# xns-ip67-ESP12-Temp.net
KiCad netlist of a schematic drawn in EAGLE
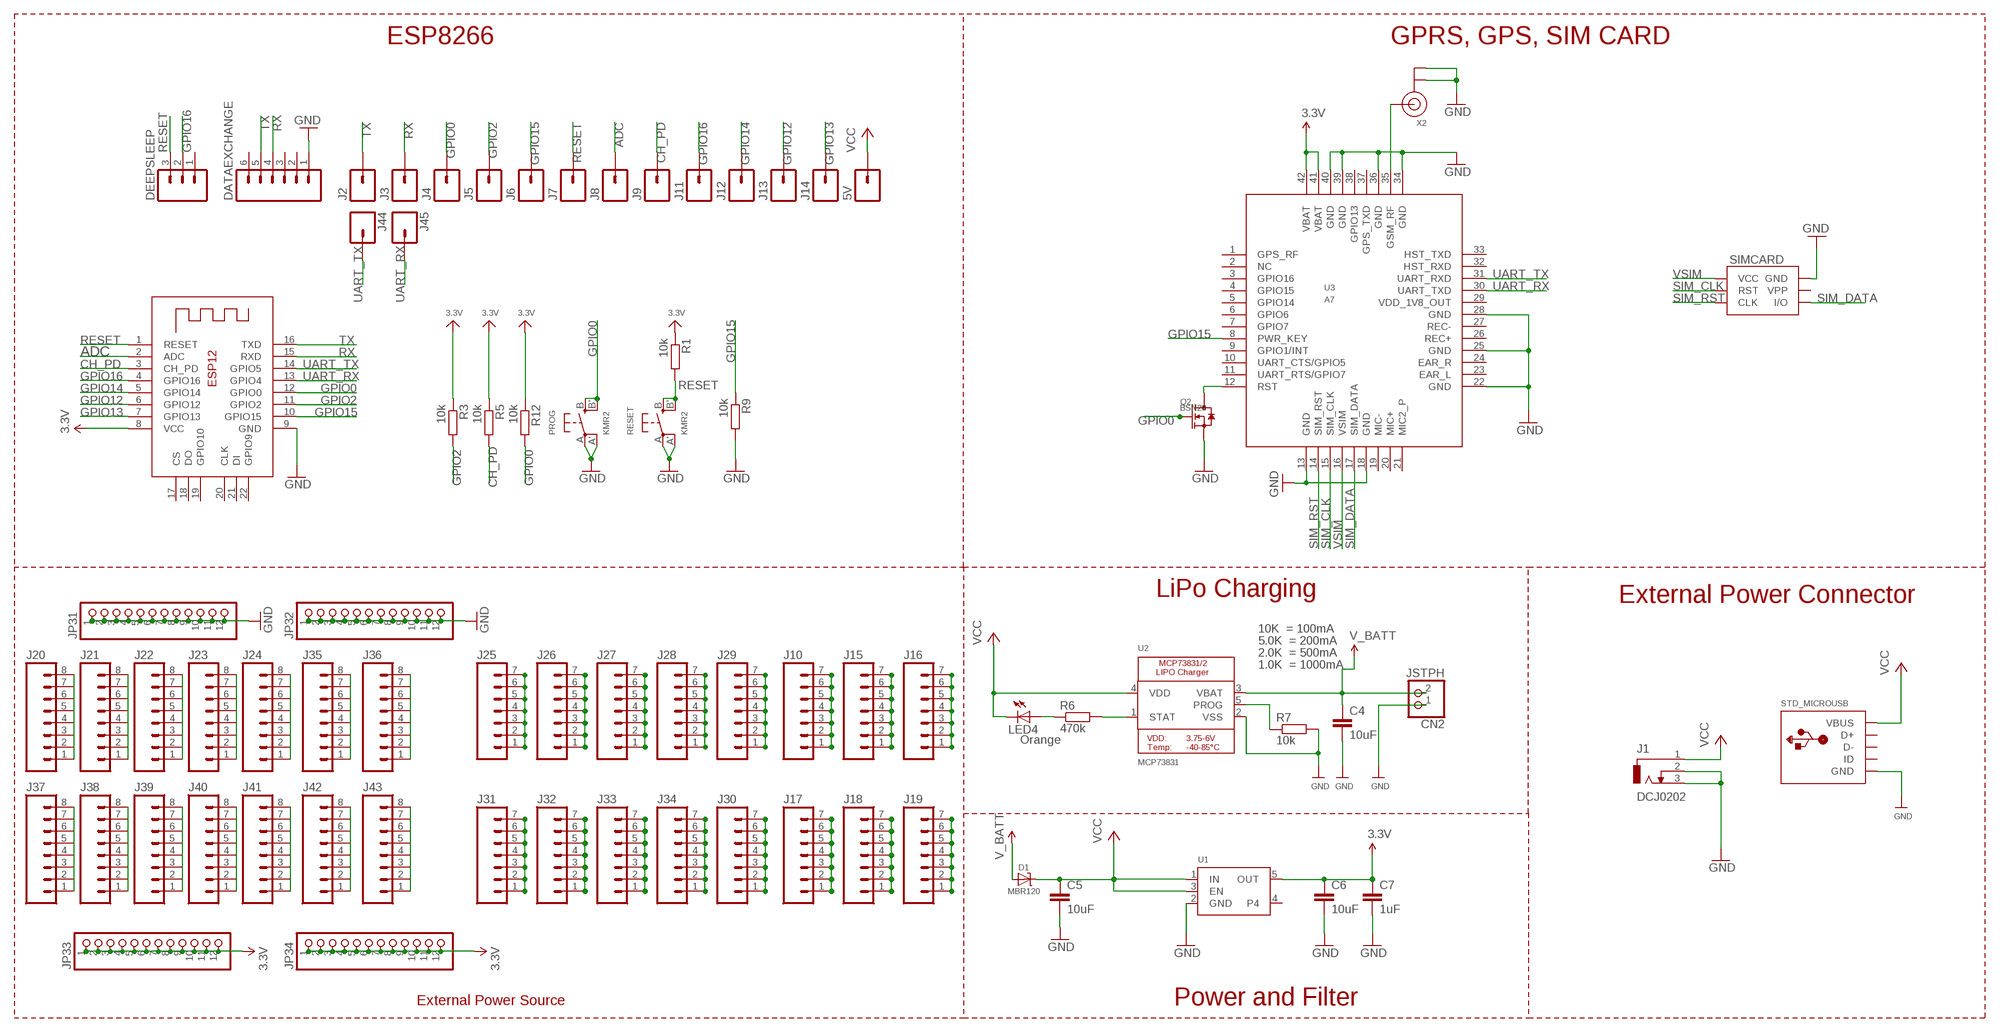
[diagram p0: schematic, sheet 1]

(export (version "E")
  (design (tool "Eeschema 10.0.6"))
  (components
    (comp (ref "5V")
      (value "M01NOSILK-KIT")
      (footprint "eagle-import:1X01NS-KIT")
      (libsource (lib "eagle-import") (part "M01NOSILK-KIT"))
    )
    (comp (ref "C4")
      (value "10uF")
      (footprint "eagle-import:C2.5-2")
      (libsource (lib "eagle-import") (part "C2.5/2"))
    )
    (comp (ref "C5")
      (value "10uF")
      (footprint "eagle-import:C2.5-2")
      (libsource (lib "eagle-import") (part "C2.5/2"))
    )
    (comp (ref "C6")
      (value "10uF")
      (footprint "eagle-import:C2.5-2")
      (libsource (lib "eagle-import") (part "C2.5/2"))
    )
    (comp (ref "C7")
      (value "1uF")
      (footprint "eagle-import:C2.5-2")
      (libsource (lib "eagle-import") (part "C2.5/2"))
    )
    (comp (ref "CN2")
      (value "JSTPH")
      (footprint "eagle-import:JSTPH2")
      (libsource (lib "eagle-import") (part "JST_2PIN"))
    )
    (comp (ref "D1")
      (value "MBR120")
      (footprint "eagle-import:SOD-123")
      (libsource (lib "eagle-import") (part "DIODE-SCHOTTKYSOD-123"))
    )
    (comp (ref "DATAEXCHANGE")
      (value "M06FEMALE_LOCK")
      (footprint "eagle-import:1X06_FEMALE_LOCK.010")
      (libsource (lib "eagle-import") (part "M06FEMALE_LOCK"))
    )
    (comp (ref "DEEPSLEEP")
      (value "M031X03_NO_SILK")
      (footprint "eagle-import:1X03_NO_SILK")
      (libsource (lib "eagle-import") (part "M031X03_NO_SILK"))
    )
    (comp (ref "J1")
      (value "DCJ0202")
      (footprint "eagle-import:DCJ0202")
      (libsource (lib "eagle-import") (part "DCJ0202"))
    )
    (comp (ref "J2")
      (value "M01NOSILK-KIT")
      (footprint "eagle-import:1X01NS-KIT")
      (libsource (lib "eagle-import") (part "M01NOSILK-KIT"))
    )
    (comp (ref "J3")
      (value "M01NOSILK-KIT")
      (footprint "eagle-import:1X01NS-KIT")
      (libsource (lib "eagle-import") (part "M01NOSILK-KIT"))
    )
    (comp (ref "J4")
      (value "M01NOSILK-KIT")
      (footprint "eagle-import:1X01NS-KIT")
      (libsource (lib "eagle-import") (part "M01NOSILK-KIT"))
    )
    (comp (ref "J5")
      (value "M01NOSILK-KIT")
      (footprint "eagle-import:1X01NS-KIT")
      (libsource (lib "eagle-import") (part "M01NOSILK-KIT"))
    )
    (comp (ref "J6")
      (value "M01NOSILK-KIT")
      (footprint "eagle-import:1X01NS-KIT")
      (libsource (lib "eagle-import") (part "M01NOSILK-KIT"))
    )
    (comp (ref "J7")
      (value "M01NOSILK-KIT")
      (footprint "eagle-import:1X01NS-KIT")
      (libsource (lib "eagle-import") (part "M01NOSILK-KIT"))
    )
    (comp (ref "J8")
      (value "M01NOSILK-KIT")
      (footprint "eagle-import:1X01NS-KIT")
      (libsource (lib "eagle-import") (part "M01NOSILK-KIT"))
    )
    (comp (ref "J9")
      (value "M01NOSILK-KIT")
      (footprint "eagle-import:1X01NS-KIT")
      (libsource (lib "eagle-import") (part "M01NOSILK-KIT"))
    )
    (comp (ref "J10")
      (value "M07NO_SILK")
      (footprint "eagle-import:1X07_NO_SILK")
      (libsource (lib "eagle-import") (part "M07NO_SILK"))
    )
    (comp (ref "J11")
      (value "M01NOSILK-KIT")
      (footprint "eagle-import:1X01NS-KIT")
      (libsource (lib "eagle-import") (part "M01NOSILK-KIT"))
    )
    (comp (ref "J12")
      (value "M01NOSILK-KIT")
      (footprint "eagle-import:1X01NS-KIT")
      (libsource (lib "eagle-import") (part "M01NOSILK-KIT"))
    )
    (comp (ref "J13")
      (value "M01NOSILK-KIT")
      (footprint "eagle-import:1X01NS-KIT")
      (libsource (lib "eagle-import") (part "M01NOSILK-KIT"))
    )
    (comp (ref "J14")
      (value "M01NOSILK-KIT")
      (footprint "eagle-import:1X01NS-KIT")
      (libsource (lib "eagle-import") (part "M01NOSILK-KIT"))
    )
    (comp (ref "J15")
      (value "M07NO_SILK")
      (footprint "eagle-import:1X07_NO_SILK")
      (libsource (lib "eagle-import") (part "M07NO_SILK"))
    )
    (comp (ref "J16")
      (value "M07NO_SILK")
      (footprint "eagle-import:1X07_NO_SILK")
      (libsource (lib "eagle-import") (part "M07NO_SILK"))
    )
    (comp (ref "J17")
      (value "M07NO_SILK")
      (footprint "eagle-import:1X07_NO_SILK")
      (libsource (lib "eagle-import") (part "M07NO_SILK"))
    )
    (comp (ref "J18")
      (value "M07NO_SILK")
      (footprint "eagle-import:1X07_NO_SILK")
      (libsource (lib "eagle-import") (part "M07NO_SILK"))
    )
    (comp (ref "J19")
      (value "M07NO_SILK")
      (footprint "eagle-import:1X07_NO_SILK")
      (libsource (lib "eagle-import") (part "M07NO_SILK"))
    )
    (comp (ref "J20")
      (value "M08NO_SILK_FEMALE_PTH")
      (footprint "eagle-import:1X08_NO_SILK")
      (libsource (lib "eagle-import") (part "M08NO_SILK_FEMALE_PTH"))
    )
    (comp (ref "J21")
      (value "M08NO_SILK_FEMALE_PTH")
      (footprint "eagle-import:1X08_NO_SILK")
      (libsource (lib "eagle-import") (part "M08NO_SILK_FEMALE_PTH"))
    )
    (comp (ref "J22")
      (value "M08NO_SILK_FEMALE_PTH")
      (footprint "eagle-import:1X08_NO_SILK")
      (libsource (lib "eagle-import") (part "M08NO_SILK_FEMALE_PTH"))
    )
    (comp (ref "J23")
      (value "M08NO_SILK_FEMALE_PTH")
      (footprint "eagle-import:1X08_NO_SILK")
      (libsource (lib "eagle-import") (part "M08NO_SILK_FEMALE_PTH"))
    )
    (comp (ref "J24")
      (value "M08NO_SILK_FEMALE_PTH")
      (footprint "eagle-import:1X08_NO_SILK")
      (libsource (lib "eagle-import") (part "M08NO_SILK_FEMALE_PTH"))
    )
    (comp (ref "J25")
      (value "M07NO_SILK")
      (footprint "eagle-import:1X07_NO_SILK")
      (libsource (lib "eagle-import") (part "M07NO_SILK"))
    )
    (comp (ref "J26")
      (value "M07NO_SILK")
      (footprint "eagle-import:1X07_NO_SILK")
      (libsource (lib "eagle-import") (part "M07NO_SILK"))
    )
    (comp (ref "J27")
      (value "M07NO_SILK")
      (footprint "eagle-import:1X07_NO_SILK")
      (libsource (lib "eagle-import") (part "M07NO_SILK"))
    )
    (comp (ref "J28")
      (value "M07NO_SILK")
      (footprint "eagle-import:1X07_NO_SILK")
      (libsource (lib "eagle-import") (part "M07NO_SILK"))
    )
    (comp (ref "J29")
      (value "M07NO_SILK")
      (footprint "eagle-import:1X07_NO_SILK")
      (libsource (lib "eagle-import") (part "M07NO_SILK"))
    )
    (comp (ref "J30")
      (value "M07NO_SILK")
      (footprint "eagle-import:1X07_NO_SILK")
      (libsource (lib "eagle-import") (part "M07NO_SILK"))
    )
    (comp (ref "J31")
      (value "M07NO_SILK")
      (footprint "eagle-import:1X07_NO_SILK")
      (libsource (lib "eagle-import") (part "M07NO_SILK"))
    )
    (comp (ref "J32")
      (value "M07NO_SILK")
      (footprint "eagle-import:1X07_NO_SILK")
      (libsource (lib "eagle-import") (part "M07NO_SILK"))
    )
    (comp (ref "J33")
      (value "M07NO_SILK")
      (footprint "eagle-import:1X07_NO_SILK")
      (libsource (lib "eagle-import") (part "M07NO_SILK"))
    )
    (comp (ref "J34")
      (value "M07NO_SILK")
      (footprint "eagle-import:1X07_NO_SILK")
      (libsource (lib "eagle-import") (part "M07NO_SILK"))
    )
    (comp (ref "J35")
      (value "M08NO_SILK_FEMALE_PTH")
      (footprint "eagle-import:1X08_NO_SILK")
      (libsource (lib "eagle-import") (part "M08NO_SILK_FEMALE_PTH"))
    )
    (comp (ref "J36")
      (value "M08NO_SILK_FEMALE_PTH")
      (footprint "eagle-import:1X08_NO_SILK")
      (libsource (lib "eagle-import") (part "M08NO_SILK_FEMALE_PTH"))
    )
    (comp (ref "J37")
      (value "M08NO_SILK_FEMALE_PTH")
      (footprint "eagle-import:1X08_NO_SILK")
      (libsource (lib "eagle-import") (part "M08NO_SILK_FEMALE_PTH"))
    )
    (comp (ref "J38")
      (value "M08NO_SILK_FEMALE_PTH")
      (footprint "eagle-import:1X08_NO_SILK")
      (libsource (lib "eagle-import") (part "M08NO_SILK_FEMALE_PTH"))
    )
    (comp (ref "J39")
      (value "M08NO_SILK_FEMALE_PTH")
      (footprint "eagle-import:1X08_NO_SILK")
      (libsource (lib "eagle-import") (part "M08NO_SILK_FEMALE_PTH"))
    )
    (comp (ref "J40")
      (value "M08NO_SILK_FEMALE_PTH")
      (footprint "eagle-import:1X08_NO_SILK")
      (libsource (lib "eagle-import") (part "M08NO_SILK_FEMALE_PTH"))
    )
    (comp (ref "J41")
      (value "M08NO_SILK_FEMALE_PTH")
      (footprint "eagle-import:1X08_NO_SILK")
      (libsource (lib "eagle-import") (part "M08NO_SILK_FEMALE_PTH"))
    )
    (comp (ref "J42")
      (value "M08NO_SILK_FEMALE_PTH")
      (footprint "eagle-import:1X08_NO_SILK")
      (libsource (lib "eagle-import") (part "M08NO_SILK_FEMALE_PTH"))
    )
    (comp (ref "J43")
      (value "M08NO_SILK_FEMALE_PTH")
      (footprint "eagle-import:1X08_NO_SILK")
      (libsource (lib "eagle-import") (part "M08NO_SILK_FEMALE_PTH"))
    )
    (comp (ref "J44")
      (value "M01NOSILK-KIT")
      (footprint "eagle-import:1X01NS-KIT")
      (libsource (lib "eagle-import") (part "M01NOSILK-KIT"))
    )
    (comp (ref "J45")
      (value "M01NOSILK-KIT")
      (footprint "eagle-import:1X01NS-KIT")
      (libsource (lib "eagle-import") (part "M01NOSILK-KIT"))
    )
    (comp (ref "JP31")
      (value "HEADER-1X12")
      (footprint "eagle-import:1X12_ROUND")
      (libsource (lib "eagle-import") (part "HEADER-1X12"))
    )
    (comp (ref "JP32")
      (value "HEADER-1X12")
      (footprint "eagle-import:1X12_ROUND")
      (libsource (lib "eagle-import") (part "HEADER-1X12"))
    )
    (comp (ref "JP33")
      (value "HEADER-1X12")
      (footprint "eagle-import:1X12_ROUND")
      (libsource (lib "eagle-import") (part "HEADER-1X12"))
    )
    (comp (ref "JP34")
      (value "HEADER-1X12")
      (footprint "eagle-import:1X12_ROUND")
      (libsource (lib "eagle-import") (part "HEADER-1X12"))
    )
    (comp (ref "LED4")
      (value "Orange")
      (footprint "eagle-import:LED5MM")
      (libsource (lib "eagle-import") (part "LED5MM"))
    )
    (comp (ref "PROG")
      (value "KMR2")
      (footprint "eagle-import:BTN_KMR2_4.6X2.8")
      (libsource (lib "eagle-import") (part "SWITCH_TACT_SMT4.6X2.8"))
    )
    (comp (ref "Q2")
      (value "BSN20")
      (footprint "eagle-import:SOT23@1")
      (libsource (lib "eagle-import") (part "MOSFET-N'SOT23'"))
    )
    (comp (ref "R1")
      (value "10k")
      (footprint "eagle-import:0204_7")
      (libsource (lib "eagle-import") (part "R0204/7"))
    )
    (comp (ref "R3")
      (value "10k")
      (footprint "eagle-import:0204_7")
      (libsource (lib "eagle-import") (part "R0204/7"))
    )
    (comp (ref "R5")
      (value "10k")
      (footprint "eagle-import:0204_7")
      (libsource (lib "eagle-import") (part "R0204/7"))
    )
    (comp (ref "R6")
      (value "470k")
      (footprint "eagle-import:0204_7")
      (libsource (lib "eagle-import") (part "R0204/7"))
    )
    (comp (ref "R7")
      (value "10k")
      (footprint "eagle-import:0204_7")
      (libsource (lib "eagle-import") (part "R0204/7"))
    )
    (comp (ref "R9")
      (value "10k")
      (footprint "eagle-import:0204_7")
      (libsource (lib "eagle-import") (part "R0204/7"))
    )
    (comp (ref "R12")
      (value "10k")
      (footprint "eagle-import:0204_7")
      (libsource (lib "eagle-import") (part "R0204/7"))
    )
    (comp (ref "RESET")
      (value "KMR2")
      (footprint "eagle-import:BTN_KMR2_4.6X2.8")
      (libsource (lib "eagle-import") (part "SWITCH_TACT_SMT4.6X2.8"))
    )
    (comp (ref "SIMCARD")
      (value "SIMHOLDERSIM")
      (footprint "eagle-import:SIMHOLDER")
      (libsource (lib "eagle-import") (part "SIMHOLDERSIM"))
    )
    (comp (ref "STD_MICROUSB")
      (value "USB_MICRO_20329_V2")
      (footprint "eagle-import:4UCONN_20329_V2")
      (libsource (lib "eagle-import") (part "USB_MICRO_20329_V2"))
    )
    (comp (ref "U1")
      (value "VREG_SOT23-5")
      (footprint "eagle-import:SOT23-5")
      (libsource (lib "eagle-import") (part "VREG_SOT23-5"))
    )
    (comp (ref "U2")
      (value "MCP73831")
      (footprint "eagle-import:SOT23-5@1")
      (libsource (lib "eagle-import") (part "MCP73831/2"))
    )
    (comp (ref "U3") (value "A7") (footprint "eagle-import:A7") (libsource (lib "eagle-import") (part "A7")))
    (comp (ref "X1")
      (value "ESP-12E")
      (footprint "eagle-import:ESP-12E")
      (libsource (lib "eagle-import") (part "ESP-12E"))
    )
    (comp (ref "X2")
      (value "ANTENNA_U.FL")
      (footprint "eagle-import:U.FL")
      (libsource (lib "eagle-import") (part "ANTENNA_U.FL"))
    )
  )
  (nets
    (net (code "1") (name "/ADC") (class "Default")
      (node (ref "J8") (pin "1") (pinfunction "1_1") (pintype "passive"))
      (node (ref "X1") (pin "2") (pinfunction "ADC_2") (pintype "passive"))
    )
    (net (code "2") (name "/CH_PD") (class "Default")
      (node (ref "J9") (pin "1") (pinfunction "1_1") (pintype "passive"))
      (node (ref "R5") (pin "2") (pinfunction "2_2") (pintype "passive"))
      (node (ref "X1") (pin "3") (pinfunction "CH_PD_3") (pintype "input"))
    )
    (net (code "3") (name "/GPIO0") (class "Default")
      (node (ref "J4") (pin "1") (pinfunction "1_1") (pintype "passive"))
      (node (ref "PROG") (pin "B") (pinfunction "S_B") (pintype "passive"))
      (node (ref "PROG") (pin "B'") (pinfunction "S1_B'") (pintype "passive"))
      (node (ref "Q2") (pin "1") (pinfunction "G_1") (pintype "passive"))
      (node (ref "R12") (pin "2") (pinfunction "2_2") (pintype "passive"))
      (node (ref "X1") (pin "12") (pinfunction "GPIO0_12") (pintype "bidirectional"))
    )
    (net (code "4") (name "/GPIO2") (class "Default")
      (node (ref "J5") (pin "1") (pinfunction "1_1") (pintype "passive"))
      (node (ref "R3") (pin "2") (pinfunction "2_2") (pintype "passive"))
      (node (ref "X1") (pin "11") (pinfunction "GPIO2_11") (pintype "bidirectional"))
    )
    (net (code "5") (name "/GPIO12") (class "Default")
      (node (ref "J13") (pin "1") (pinfunction "1_1") (pintype "passive"))
      (node (ref "X1") (pin "6") (pinfunction "GPIO12_6") (pintype "bidirectional"))
    )
    (net (code "6") (name "/GPIO13") (class "Default")
      (node (ref "J14") (pin "1") (pinfunction "1_1") (pintype "passive"))
      (node (ref "X1") (pin "7") (pinfunction "GPIO13_7") (pintype "bidirectional"))
    )
    (net (code "7") (name "/GPIO14") (class "Default")
      (node (ref "J12") (pin "1") (pinfunction "1_1") (pintype "passive"))
      (node (ref "X1") (pin "5") (pinfunction "GPIO14_5") (pintype "bidirectional"))
    )
    (net (code "8") (name "/GPIO15") (class "Default")
      (node (ref "J6") (pin "1") (pinfunction "1_1") (pintype "passive"))
      (node (ref "R9") (pin "1") (pinfunction "1_1") (pintype "passive"))
      (node (ref "U3") (pin "8") (pinfunction "PWR_KEY_8") (pintype "bidirectional"))
      (node (ref "X1") (pin "10") (pinfunction "GPIO15_10") (pintype "bidirectional"))
    )
    (net (code "9") (name "/GPIO16") (class "Default")
      (node (ref "DEEPSLEEP") (pin "2") (pinfunction "2_2") (pintype "passive"))
      (node (ref "J11") (pin "1") (pinfunction "1_1") (pintype "passive"))
      (node (ref "X1") (pin "4") (pinfunction "GPIO16_4") (pintype "bidirectional"))
    )
    (net (code "10") (name "/RESET") (class "Default")
      (node (ref "DEEPSLEEP") (pin "3") (pinfunction "3_3") (pintype "passive"))
      (node (ref "J7") (pin "1") (pinfunction "1_1") (pintype "passive"))
      (node (ref "R1") (pin "2") (pinfunction "2_2") (pintype "passive"))
      (node (ref "RESET") (pin "B") (pinfunction "S_B") (pintype "passive"))
      (node (ref "RESET") (pin "B'") (pinfunction "S1_B'") (pintype "passive"))
      (node (ref "X1") (pin "1") (pinfunction "RESET_1") (pintype "input"))
    )
    (net (code "11") (name "/RX") (class "Default")
      (node (ref "DATAEXCHANGE") (pin "4") (pinfunction "4_4") (pintype "passive"))
      (node (ref "J3") (pin "1") (pinfunction "1_1") (pintype "passive"))
      (node (ref "X1") (pin "15") (pinfunction "RXD_15") (pintype "input"))
    )
    (net (code "12") (name "/SIM_CLK") (class "Default")
      (node (ref "SIMCARD") (pin "C2") (pinfunction "RST_C2") (pintype "input"))
      (node (ref "U3") (pin "15") (pinfunction "SIM_CLK_15") (pintype "bidirectional"))
    )
    (net (code "13") (name "/SIM_DATA") (class "Default")
      (node (ref "SIMCARD") (pin "C7") (pinfunction "I/O_C7") (pintype "bidirectional"))
      (node (ref "U3") (pin "17") (pinfunction "SIM_DATA_17") (pintype "bidirectional"))
    )
    (net (code "14") (name "/SIM_RST") (class "Default")
      (node (ref "SIMCARD") (pin "C3") (pinfunction "CLK_C3") (pintype "input"))
      (node (ref "U3") (pin "14") (pinfunction "SIM_RST_14") (pintype "bidirectional"))
    )
    (net (code "15") (name "/TX") (class "Default")
      (node (ref "DATAEXCHANGE") (pin "5") (pinfunction "5_5") (pintype "passive"))
      (node (ref "J2") (pin "1") (pinfunction "1_1") (pintype "passive"))
      (node (ref "X1") (pin "16") (pinfunction "TXD_16") (pintype "output"))
    )
    (net (code "16") (name "/UART_RX") (class "Default")
      (node (ref "J45") (pin "1") (pinfunction "1_1") (pintype "passive"))
      (node (ref "U3") (pin "30") (pinfunction "UART_TXD_30") (pintype "bidirectional"))
      (node (ref "X1") (pin "13") (pinfunction "GPIO4_13") (pintype "bidirectional"))
    )
    (net (code "17") (name "/UART_TX") (class "Default")
      (node (ref "J44") (pin "1") (pinfunction "1_1") (pintype "passive"))
      (node (ref "U3") (pin "31") (pinfunction "UART_RXD_31") (pintype "bidirectional"))
      (node (ref "X1") (pin "14") (pinfunction "GPIO5_14") (pintype "bidirectional"))
    )
    (net (code "18") (name "/VSIM") (class "Default")
      (node (ref "SIMCARD") (pin "C1") (pinfunction "VCC_C1") (pintype "power_in"))
      (node (ref "U3") (pin "16") (pinfunction "VSIM_16") (pintype "bidirectional"))
    )
    (net (code "19") (name "3.3V") (class "Default")
      (node (ref "C6") (pin "1") (pinfunction "1_1") (pintype "passive"))
      (node (ref "C7") (pin "1") (pinfunction "1_1") (pintype "passive"))
      (node (ref "JP33") (pin "1") (pinfunction "1_1") (pintype "passive"))
      (node (ref "JP33") (pin "10") (pinfunction "10_10") (pintype "passive"))
      (node (ref "JP33") (pin "11") (pinfunction "11_11") (pintype "passive"))
      (node (ref "JP33") (pin "12") (pinfunction "12_12") (pintype "passive"))
      (node (ref "JP33") (pin "2") (pinfunction "2_2") (pintype "passive"))
      (node (ref "JP33") (pin "3") (pinfunction "3_3") (pintype "passive"))
      (node (ref "JP33") (pin "4") (pinfunction "4_4") (pintype "passive"))
      (node (ref "JP33") (pin "5") (pinfunction "5_5") (pintype "passive"))
      (node (ref "JP33") (pin "6") (pinfunction "6_6") (pintype "passive"))
      (node (ref "JP33") (pin "7") (pinfunction "7_7") (pintype "passive"))
      (node (ref "JP33") (pin "8") (pinfunction "8_8") (pintype "passive"))
      (node (ref "JP33") (pin "9") (pinfunction "9_9") (pintype "passive"))
      (node (ref "JP34") (pin "1") (pinfunction "1_1") (pintype "passive"))
      (node (ref "JP34") (pin "10") (pinfunction "10_10") (pintype "passive"))
      (node (ref "JP34") (pin "11") (pinfunction "11_11") (pintype "passive"))
      (node (ref "JP34") (pin "12") (pinfunction "12_12") (pintype "passive"))
      (node (ref "JP34") (pin "2") (pinfunction "2_2") (pintype "passive"))
      (node (ref "JP34") (pin "3") (pinfunction "3_3") (pintype "passive"))
      (node (ref "JP34") (pin "4") (pinfunction "4_4") (pintype "passive"))
      (node (ref "JP34") (pin "5") (pinfunction "5_5") (pintype "passive"))
      (node (ref "JP34") (pin "6") (pinfunction "6_6") (pintype "passive"))
      (node (ref "JP34") (pin "7") (pinfunction "7_7") (pintype "passive"))
      (node (ref "JP34") (pin "8") (pinfunction "8_8") (pintype "passive"))
      (node (ref "JP34") (pin "9") (pinfunction "9_9") (pintype "passive"))
      (node (ref "R1") (pin "1") (pinfunction "1_1") (pintype "passive"))
      (node (ref "R12") (pin "1") (pinfunction "1_1") (pintype "passive"))
      (node (ref "R3") (pin "1") (pinfunction "1_1") (pintype "passive"))
      (node (ref "R5") (pin "1") (pinfunction "1_1") (pintype "passive"))
      (node (ref "U1") (pin "5") (pinfunction "OUT_5") (pintype "power_in"))
      (node (ref "U3") (pin "41") (pinfunction "VBAT_41") (pintype "bidirectional"))
      (node (ref "U3") (pin "42") (pinfunction "VBAT_42") (pintype "bidirectional"))
      (node (ref "X1") (pin "8") (pinfunction "VCC_8") (pintype "power_in"))
    )
    (net (code "20") (name "GND") (class "Default")
      (node (ref "C4") (pin "2") (pinfunction "2_2") (pintype "passive"))
      (node (ref "C5") (pin "2") (pinfunction "2_2") (pintype "passive"))
      (node (ref "C6") (pin "2") (pinfunction "2_2") (pintype "passive"))
      (node (ref "C7") (pin "2") (pinfunction "2_2") (pintype "passive"))
      (node (ref "CN2") (pin "1") (pinfunction "1_1") (pintype "passive"))
      (node (ref "DATAEXCHANGE") (pin "1") (pinfunction "1_1") (pintype "passive"))
      (node (ref "J1") (pin "2") (pinfunction "2_2") (pintype "passive"))
      (node (ref "J1") (pin "3") (pinfunction "3_3") (pintype "passive"))
      (node (ref "JP31") (pin "1") (pinfunction "1_1") (pintype "passive"))
      (node (ref "JP31") (pin "10") (pinfunction "10_10") (pintype "passive"))
      (node (ref "JP31") (pin "11") (pinfunction "11_11") (pintype "passive"))
      (node (ref "JP31") (pin "12") (pinfunction "12_12") (pintype "passive"))
      (node (ref "JP31") (pin "2") (pinfunction "2_2") (pintype "passive"))
      (node (ref "JP31") (pin "3") (pinfunction "3_3") (pintype "passive"))
      (node (ref "JP31") (pin "4") (pinfunction "4_4") (pintype "passive"))
      (node (ref "JP31") (pin "5") (pinfunction "5_5") (pintype "passive"))
      (node (ref "JP31") (pin "6") (pinfunction "6_6") (pintype "passive"))
      (node (ref "JP31") (pin "7") (pinfunction "7_7") (pintype "passive"))
      (node (ref "JP31") (pin "8") (pinfunction "8_8") (pintype "passive"))
      (node (ref "JP31") (pin "9") (pinfunction "9_9") (pintype "passive"))
      (node (ref "JP32") (pin "1") (pinfunction "1_1") (pintype "passive"))
      (node (ref "JP32") (pin "10") (pinfunction "10_10") (pintype "passive"))
      (node (ref "JP32") (pin "11") (pinfunction "11_11") (pintype "passive"))
      (node (ref "JP32") (pin "12") (pinfunction "12_12") (pintype "passive"))
      (node (ref "JP32") (pin "2") (pinfunction "2_2") (pintype "passive"))
      (node (ref "JP32") (pin "3") (pinfunction "3_3") (pintype "passive"))
      (node (ref "JP32") (pin "4") (pinfunction "4_4") (pintype "passive"))
      (node (ref "JP32") (pin "5") (pinfunction "5_5") (pintype "passive"))
      (node (ref "JP32") (pin "6") (pinfunction "6_6") (pintype "passive"))
      (node (ref "JP32") (pin "7") (pinfunction "7_7") (pintype "passive"))
      (node (ref "JP32") (pin "8") (pinfunction "8_8") (pintype "passive"))
      (node (ref "JP32") (pin "9") (pinfunction "9_9") (pintype "passive"))
      (node (ref "PROG") (pin "A") (pinfunction "P_A") (pintype "passive"))
      (node (ref "PROG") (pin "A'") (pinfunction "P1_A'") (pintype "passive"))
      (node (ref "Q2") (pin "2") (pinfunction "S_2") (pintype "passive"))
      (node (ref "R7") (pin "2") (pinfunction "2_2") (pintype "passive"))
      (node (ref "R9") (pin "2") (pinfunction "2_2") (pintype "passive"))
      (node (ref "RESET") (pin "A") (pinfunction "P_A") (pintype "passive"))
      (node (ref "RESET") (pin "A'") (pinfunction "P1_A'") (pintype "passive"))
      (node (ref "SIMCARD") (pin "C5") (pinfunction "GND_C5") (pintype "power_in"))
      (node (ref "STD_MICROUSB") (pin "BASE@1") (pinfunction "GND_BASE@1") (pintype "power_in"))
      (node (ref "STD_MICROUSB") (pin "BASE@2") (pinfunction "GND_BASE@2") (pintype "power_in"))
      (node (ref "STD_MICROUSB") (pin "GND") (pinfunction "GND_GND") (pintype "power_in"))
      (node (ref "STD_MICROUSB") (pin "SPRT@1") (pinfunction "GND_SPRT@1") (pintype "power_in"))
      (node (ref "STD_MICROUSB") (pin "SPRT@2") (pinfunction "GND_SPRT@2") (pintype "power_in"))
      (node (ref "STD_MICROUSB") (pin "SPRT@3") (pinfunction "GND_SPRT@3") (pintype "power_in"))
      (node (ref "STD_MICROUSB") (pin "SPRT@4") (pinfunction "GND_SPRT@4") (pintype "power_in"))
      (node (ref "U1") (pin "2") (pinfunction "GND_2") (pintype "power_in"))
      (node (ref "U2") (pin "2") (pinfunction "VSS_2") (pintype "power_in"))
      (node (ref "U3") (pin "13") (pinfunction "GND_13") (pintype "bidirectional"))
      (node (ref "U3") (pin "18") (pinfunction "GND_18") (pintype "bidirectional"))
      (node (ref "U3") (pin "22") (pinfunction "GND_22") (pintype "bidirectional"))
      (node (ref "U3") (pin "25") (pinfunction "GND_25") (pintype "bidirectional"))
      (node (ref "U3") (pin "28") (pinfunction "GND_28") (pintype "bidirectional"))
      (node (ref "U3") (pin "34") (pinfunction "GND_34") (pintype "bidirectional"))
      (node (ref "U3") (pin "36") (pinfunction "GND_36") (pintype "bidirectional"))
      (node (ref "U3") (pin "39") (pinfunction "GND_39") (pintype "bidirectional"))
      (node (ref "U3") (pin "40") (pinfunction "GND_40") (pintype "bidirectional"))
      (node (ref "X1") (pin "9") (pinfunction "GND_9") (pintype "power_in"))
      (node (ref "X2") (pin "1") (pinfunction "GND_1") (pintype "passive"))
      (node (ref "X2") (pin "2") (pinfunction "GND_2") (pintype "passive"))
    )
    (net (code "21") (name "Net-(J10-Pad1)") (class "Default")
      (node (ref "J10") (pin "1") (pinfunction "1_1") (pintype "passive"))
      (node (ref "J10") (pin "2") (pinfunction "2_2") (pintype "passive"))
      (node (ref "J10") (pin "3") (pinfunction "3_3") (pintype "passive"))
      (node (ref "J10") (pin "4") (pinfunction "4_4") (pintype "passive"))
      (node (ref "J10") (pin "5") (pinfunction "5_5") (pintype "passive"))
      (node (ref "J10") (pin "6") (pinfunction "6_6") (pintype "passive"))
      (node (ref "J10") (pin "7") (pinfunction "7_7") (pintype "passive"))
    )
    (net (code "22") (name "Net-(J15-Pad1)") (class "Default")
      (node (ref "J15") (pin "1") (pinfunction "1_1") (pintype "passive"))
      (node (ref "J15") (pin "2") (pinfunction "2_2") (pintype "passive"))
      (node (ref "J15") (pin "3") (pinfunction "3_3") (pintype "passive"))
      (node (ref "J15") (pin "4") (pinfunction "4_4") (pintype "passive"))
      (node (ref "J15") (pin "5") (pinfunction "5_5") (pintype "passive"))
      (node (ref "J15") (pin "6") (pinfunction "6_6") (pintype "passive"))
      (node (ref "J15") (pin "7") (pinfunction "7_7") (pintype "passive"))
    )
    (net (code "23") (name "Net-(J16-Pad1)") (class "Default")
      (node (ref "J16") (pin "1") (pinfunction "1_1") (pintype "passive"))
      (node (ref "J16") (pin "2") (pinfunction "2_2") (pintype "passive"))
      (node (ref "J16") (pin "3") (pinfunction "3_3") (pintype "passive"))
      (node (ref "J16") (pin "4") (pinfunction "4_4") (pintype "passive"))
      (node (ref "J16") (pin "5") (pinfunction "5_5") (pintype "passive"))
      (node (ref "J16") (pin "6") (pinfunction "6_6") (pintype "passive"))
      (node (ref "J16") (pin "7") (pinfunction "7_7") (pintype "passive"))
    )
    (net (code "24") (name "Net-(J17-Pad1)") (class "Default")
      (node (ref "J17") (pin "1") (pinfunction "1_1") (pintype "passive"))
      (node (ref "J17") (pin "2") (pinfunction "2_2") (pintype "passive"))
      (node (ref "J17") (pin "3") (pinfunction "3_3") (pintype "passive"))
      (node (ref "J17") (pin "4") (pinfunction "4_4") (pintype "passive"))
      (node (ref "J17") (pin "5") (pinfunction "5_5") (pintype "passive"))
      (node (ref "J17") (pin "6") (pinfunction "6_6") (pintype "passive"))
      (node (ref "J17") (pin "7") (pinfunction "7_7") (pintype "passive"))
    )
    (net (code "25") (name "Net-(J18-Pad1)") (class "Default")
      (node (ref "J18") (pin "1") (pinfunction "1_1") (pintype "passive"))
      (node (ref "J18") (pin "2") (pinfunction "2_2") (pintype "passive"))
      (node (ref "J18") (pin "3") (pinfunction "3_3") (pintype "passive"))
      (node (ref "J18") (pin "4") (pinfunction "4_4") (pintype "passive"))
      (node (ref "J18") (pin "5") (pinfunction "5_5") (pintype "passive"))
      (node (ref "J18") (pin "6") (pinfunction "6_6") (pintype "passive"))
      (node (ref "J18") (pin "7") (pinfunction "7_7") (pintype "passive"))
    )
    (net (code "26") (name "Net-(J19-Pad1)") (class "Default")
      (node (ref "J19") (pin "1") (pinfunction "1_1") (pintype "passive"))
      (node (ref "J19") (pin "2") (pinfunction "2_2") (pintype "passive"))
      (node (ref "J19") (pin "3") (pinfunction "3_3") (pintype "passive"))
      (node (ref "J19") (pin "4") (pinfunction "4_4") (pintype "passive"))
      (node (ref "J19") (pin "5") (pinfunction "5_5") (pintype "passive"))
      (node (ref "J19") (pin "6") (pinfunction "6_6") (pintype "passive"))
      (node (ref "J19") (pin "7") (pinfunction "7_7") (pintype "passive"))
    )
    (net (code "27") (name "Net-(J20-Pad1)") (class "Default")
      (node (ref "J20") (pin "1") (pinfunction "1_1") (pintype "passive"))
      (node (ref "J20") (pin "2") (pinfunction "2_2") (pintype "passive"))
      (node (ref "J20") (pin "3") (pinfunction "3_3") (pintype "passive"))
      (node (ref "J20") (pin "4") (pinfunction "4_4") (pintype "passive"))
      (node (ref "J20") (pin "5") (pinfunction "5_5") (pintype "passive"))
      (node (ref "J20") (pin "6") (pinfunction "6_6") (pintype "passive"))
      (node (ref "J20") (pin "7") (pinfunction "7_7") (pintype "passive"))
      (node (ref "J20") (pin "8") (pinfunction "8_8") (pintype "passive"))
    )
    (net (code "28") (name "Net-(J21-Pad1)") (class "Default")
      (node (ref "J21") (pin "1") (pinfunction "1_1") (pintype "passive"))
      (node (ref "J21") (pin "2") (pinfunction "2_2") (pintype "passive"))
      (node (ref "J21") (pin "3") (pinfunction "3_3") (pintype "passive"))
      (node (ref "J21") (pin "4") (pinfunction "4_4") (pintype "passive"))
      (node (ref "J21") (pin "5") (pinfunction "5_5") (pintype "passive"))
      (node (ref "J21") (pin "6") (pinfunction "6_6") (pintype "passive"))
      (node (ref "J21") (pin "7") (pinfunction "7_7") (pintype "passive"))
      (node (ref "J21") (pin "8") (pinfunction "8_8") (pintype "passive"))
    )
    (net (code "29") (name "Net-(J22-Pad1)") (class "Default")
      (node (ref "J22") (pin "1") (pinfunction "1_1") (pintype "passive"))
      (node (ref "J22") (pin "2") (pinfunction "2_2") (pintype "passive"))
      (node (ref "J22") (pin "3") (pinfunction "3_3") (pintype "passive"))
      (node (ref "J22") (pin "4") (pinfunction "4_4") (pintype "passive"))
      (node (ref "J22") (pin "5") (pinfunction "5_5") (pintype "passive"))
      (node (ref "J22") (pin "6") (pinfunction "6_6") (pintype "passive"))
      (node (ref "J22") (pin "7") (pinfunction "7_7") (pintype "passive"))
      (node (ref "J22") (pin "8") (pinfunction "8_8") (pintype "passive"))
    )
    (net (code "30") (name "Net-(J23-Pad1)") (class "Default")
      (node (ref "J23") (pin "1") (pinfunction "1_1") (pintype "passive"))
      (node (ref "J23") (pin "2") (pinfunction "2_2") (pintype "passive"))
      (node (ref "J23") (pin "3") (pinfunction "3_3") (pintype "passive"))
      (node (ref "J23") (pin "4") (pinfunction "4_4") (pintype "passive"))
      (node (ref "J23") (pin "5") (pinfunction "5_5") (pintype "passive"))
      (node (ref "J23") (pin "6") (pinfunction "6_6") (pintype "passive"))
      (node (ref "J23") (pin "7") (pinfunction "7_7") (pintype "passive"))
      (node (ref "J23") (pin "8") (pinfunction "8_8") (pintype "passive"))
    )
    (net (code "31") (name "Net-(J24-Pad1)") (class "Default")
      (node (ref "J24") (pin "1") (pinfunction "1_1") (pintype "passive"))
      (node (ref "J24") (pin "2") (pinfunction "2_2") (pintype "passive"))
      (node (ref "J24") (pin "3") (pinfunction "3_3") (pintype "passive"))
      (node (ref "J24") (pin "4") (pinfunction "4_4") (pintype "passive"))
      (node (ref "J24") (pin "5") (pinfunction "5_5") (pintype "passive"))
      (node (ref "J24") (pin "6") (pinfunction "6_6") (pintype "passive"))
      (node (ref "J24") (pin "7") (pinfunction "7_7") (pintype "passive"))
      (node (ref "J24") (pin "8") (pinfunction "8_8") (pintype "passive"))
    )
    (net (code "32") (name "Net-(J25-Pad1)") (class "Default")
      (node (ref "J25") (pin "1") (pinfunction "1_1") (pintype "passive"))
      (node (ref "J25") (pin "2") (pinfunction "2_2") (pintype "passive"))
      (node (ref "J25") (pin "3") (pinfunction "3_3") (pintype "passive"))
      (node (ref "J25") (pin "4") (pinfunction "4_4") (pintype "passive"))
      (node (ref "J25") (pin "5") (pinfunction "5_5") (pintype "passive"))
      (node (ref "J25") (pin "6") (pinfunction "6_6") (pintype "passive"))
      (node (ref "J25") (pin "7") (pinfunction "7_7") (pintype "passive"))
    )
    (net (code "33") (name "Net-(J26-Pad1)") (class "Default")
      (node (ref "J26") (pin "1") (pinfunction "1_1") (pintype "passive"))
      (node (ref "J26") (pin "2") (pinfunction "2_2") (pintype "passive"))
      (node (ref "J26") (pin "3") (pinfunction "3_3") (pintype "passive"))
      (node (ref "J26") (pin "4") (pinfunction "4_4") (pintype "passive"))
      (node (ref "J26") (pin "5") (pinfunction "5_5") (pintype "passive"))
      (node (ref "J26") (pin "6") (pinfunction "6_6") (pintype "passive"))
      (node (ref "J26") (pin "7") (pinfunction "7_7") (pintype "passive"))
    )
    (net (code "34") (name "Net-(J27-Pad1)") (class "Default")
      (node (ref "J27") (pin "1") (pinfunction "1_1") (pintype "passive"))
      (node (ref "J27") (pin "2") (pinfunction "2_2") (pintype "passive"))
      (node (ref "J27") (pin "3") (pinfunction "3_3") (pintype "passive"))
      (node (ref "J27") (pin "4") (pinfunction "4_4") (pintype "passive"))
      (node (ref "J27") (pin "5") (pinfunction "5_5") (pintype "passive"))
      (node (ref "J27") (pin "6") (pinfunction "6_6") (pintype "passive"))
      (node (ref "J27") (pin "7") (pinfunction "7_7") (pintype "passive"))
    )
    (net (code "35") (name "Net-(J28-Pad1)") (class "Default")
      (node (ref "J28") (pin "1") (pinfunction "1_1") (pintype "passive"))
      (node (ref "J28") (pin "2") (pinfunction "2_2") (pintype "passive"))
      (node (ref "J28") (pin "3") (pinfunction "3_3") (pintype "passive"))
      (node (ref "J28") (pin "4") (pinfunction "4_4") (pintype "passive"))
      (node (ref "J28") (pin "5") (pinfunction "5_5") (pintype "passive"))
      (node (ref "J28") (pin "6") (pinfunction "6_6") (pintype "passive"))
      (node (ref "J28") (pin "7") (pinfunction "7_7") (pintype "passive"))
    )
    (net (code "36") (name "Net-(J29-Pad1)") (class "Default")
      (node (ref "J29") (pin "1") (pinfunction "1_1") (pintype "passive"))
      (node (ref "J29") (pin "2") (pinfunction "2_2") (pintype "passive"))
      (node (ref "J29") (pin "3") (pinfunction "3_3") (pintype "passive"))
      (node (ref "J29") (pin "4") (pinfunction "4_4") (pintype "passive"))
      (node (ref "J29") (pin "5") (pinfunction "5_5") (pintype "passive"))
      (node (ref "J29") (pin "6") (pinfunction "6_6") (pintype "passive"))
      (node (ref "J29") (pin "7") (pinfunction "7_7") (pintype "passive"))
    )
    (net (code "37") (name "Net-(J30-Pad1)") (class "Default")
      (node (ref "J30") (pin "1") (pinfunction "1_1") (pintype "passive"))
      (node (ref "J30") (pin "2") (pinfunction "2_2") (pintype "passive"))
      (node (ref "J30") (pin "3") (pinfunction "3_3") (pintype "passive"))
      (node (ref "J30") (pin "4") (pinfunction "4_4") (pintype "passive"))
      (node (ref "J30") (pin "5") (pinfunction "5_5") (pintype "passive"))
      (node (ref "J30") (pin "6") (pinfunction "6_6") (pintype "passive"))
      (node (ref "J30") (pin "7") (pinfunction "7_7") (pintype "passive"))
    )
    (net (code "38") (name "Net-(J31-Pad1)") (class "Default")
      (node (ref "J31") (pin "1") (pinfunction "1_1") (pintype "passive"))
      (node (ref "J31") (pin "2") (pinfunction "2_2") (pintype "passive"))
      (node (ref "J31") (pin "3") (pinfunction "3_3") (pintype "passive"))
      (node (ref "J31") (pin "4") (pinfunction "4_4") (pintype "passive"))
      (node (ref "J31") (pin "5") (pinfunction "5_5") (pintype "passive"))
      (node (ref "J31") (pin "6") (pinfunction "6_6") (pintype "passive"))
      (node (ref "J31") (pin "7") (pinfunction "7_7") (pintype "passive"))
    )
    (net (code "39") (name "Net-(J32-Pad1)") (class "Default")
      (node (ref "J32") (pin "1") (pinfunction "1_1") (pintype "passive"))
      (node (ref "J32") (pin "2") (pinfunction "2_2") (pintype "passive"))
      (node (ref "J32") (pin "3") (pinfunction "3_3") (pintype "passive"))
      (node (ref "J32") (pin "4") (pinfunction "4_4") (pintype "passive"))
      (node (ref "J32") (pin "5") (pinfunction "5_5") (pintype "passive"))
      (node (ref "J32") (pin "6") (pinfunction "6_6") (pintype "passive"))
      (node (ref "J32") (pin "7") (pinfunction "7_7") (pintype "passive"))
    )
    (net (code "40") (name "Net-(J33-Pad1)") (class "Default")
      (node (ref "J33") (pin "1") (pinfunction "1_1") (pintype "passive"))
      (node (ref "J33") (pin "2") (pinfunction "2_2") (pintype "passive"))
      (node (ref "J33") (pin "3") (pinfunction "3_3") (pintype "passive"))
      (node (ref "J33") (pin "4") (pinfunction "4_4") (pintype "passive"))
      (node (ref "J33") (pin "5") (pinfunction "5_5") (pintype "passive"))
      (node (ref "J33") (pin "6") (pinfunction "6_6") (pintype "passive"))
      (node (ref "J33") (pin "7") (pinfunction "7_7") (pintype "passive"))
    )
    (net (code "41") (name "Net-(J34-Pad1)") (class "Default")
      (node (ref "J34") (pin "1") (pinfunction "1_1") (pintype "passive"))
      (node (ref "J34") (pin "2") (pinfunction "2_2") (pintype "passive"))
      (node (ref "J34") (pin "3") (pinfunction "3_3") (pintype "passive"))
      (node (ref "J34") (pin "4") (pinfunction "4_4") (pintype "passive"))
      (node (ref "J34") (pin "5") (pinfunction "5_5") (pintype "passive"))
      (node (ref "J34") (pin "6") (pinfunction "6_6") (pintype "passive"))
      (node (ref "J34") (pin "7") (pinfunction "7_7") (pintype "passive"))
    )
    (net (code "42") (name "Net-(J35-Pad1)") (class "Default")
      (node (ref "J35") (pin "1") (pinfunction "1_1") (pintype "passive"))
      (node (ref "J35") (pin "2") (pinfunction "2_2") (pintype "passive"))
      (node (ref "J35") (pin "3") (pinfunction "3_3") (pintype "passive"))
      (node (ref "J35") (pin "4") (pinfunction "4_4") (pintype "passive"))
      (node (ref "J35") (pin "5") (pinfunction "5_5") (pintype "passive"))
      (node (ref "J35") (pin "6") (pinfunction "6_6") (pintype "passive"))
      (node (ref "J35") (pin "7") (pinfunction "7_7") (pintype "passive"))
      (node (ref "J35") (pin "8") (pinfunction "8_8") (pintype "passive"))
    )
    (net (code "43") (name "Net-(J36-Pad1)") (class "Default")
      (node (ref "J36") (pin "1") (pinfunction "1_1") (pintype "passive"))
      (node (ref "J36") (pin "2") (pinfunction "2_2") (pintype "passive"))
      (node (ref "J36") (pin "3") (pinfunction "3_3") (pintype "passive"))
      (node (ref "J36") (pin "4") (pinfunction "4_4") (pintype "passive"))
      (node (ref "J36") (pin "5") (pinfunction "5_5") (pintype "passive"))
      (node (ref "J36") (pin "6") (pinfunction "6_6") (pintype "passive"))
      (node (ref "J36") (pin "7") (pinfunction "7_7") (pintype "passive"))
      (node (ref "J36") (pin "8") (pinfunction "8_8") (pintype "passive"))
    )
    (net (code "44") (name "Net-(J37-Pad1)") (class "Default")
      (node (ref "J37") (pin "1") (pinfunction "1_1") (pintype "passive"))
      (node (ref "J37") (pin "2") (pinfunction "2_2") (pintype "passive"))
      (node (ref "J37") (pin "3") (pinfunction "3_3") (pintype "passive"))
      (node (ref "J37") (pin "4") (pinfunction "4_4") (pintype "passive"))
      (node (ref "J37") (pin "5") (pinfunction "5_5") (pintype "passive"))
      (node (ref "J37") (pin "6") (pinfunction "6_6") (pintype "passive"))
      (node (ref "J37") (pin "7") (pinfunction "7_7") (pintype "passive"))
      (node (ref "J37") (pin "8") (pinfunction "8_8") (pintype "passive"))
    )
    (net (code "45") (name "Net-(J38-Pad1)") (class "Default")
      (node (ref "J38") (pin "1") (pinfunction "1_1") (pintype "passive"))
      (node (ref "J38") (pin "2") (pinfunction "2_2") (pintype "passive"))
      (node (ref "J38") (pin "3") (pinfunction "3_3") (pintype "passive"))
      (node (ref "J38") (pin "4") (pinfunction "4_4") (pintype "passive"))
      (node (ref "J38") (pin "5") (pinfunction "5_5") (pintype "passive"))
      (node (ref "J38") (pin "6") (pinfunction "6_6") (pintype "passive"))
      (node (ref "J38") (pin "7") (pinfunction "7_7") (pintype "passive"))
      (node (ref "J38") (pin "8") (pinfunction "8_8") (pintype "passive"))
    )
    (net (code "46") (name "Net-(J39-Pad1)") (class "Default")
      (node (ref "J39") (pin "1") (pinfunction "1_1") (pintype "passive"))
      (node (ref "J39") (pin "2") (pinfunction "2_2") (pintype "passive"))
      (node (ref "J39") (pin "3") (pinfunction "3_3") (pintype "passive"))
      (node (ref "J39") (pin "4") (pinfunction "4_4") (pintype "passive"))
      (node (ref "J39") (pin "5") (pinfunction "5_5") (pintype "passive"))
      (node (ref "J39") (pin "6") (pinfunction "6_6") (pintype "passive"))
      (node (ref "J39") (pin "7") (pinfunction "7_7") (pintype "passive"))
      (node (ref "J39") (pin "8") (pinfunction "8_8") (pintype "passive"))
    )
    (net (code "47") (name "Net-(J40-Pad1)") (class "Default")
      (node (ref "J40") (pin "1") (pinfunction "1_1") (pintype "passive"))
      (node (ref "J40") (pin "2") (pinfunction "2_2") (pintype "passive"))
      (node (ref "J40") (pin "3") (pinfunction "3_3") (pintype "passive"))
      (node (ref "J40") (pin "4") (pinfunction "4_4") (pintype "passive"))
      (node (ref "J40") (pin "5") (pinfunction "5_5") (pintype "passive"))
      (node (ref "J40") (pin "6") (pinfunction "6_6") (pintype "passive"))
      (node (ref "J40") (pin "7") (pinfunction "7_7") (pintype "passive"))
      (node (ref "J40") (pin "8") (pinfunction "8_8") (pintype "passive"))
    )
    (net (code "48") (name "Net-(J41-Pad1)") (class "Default")
      (node (ref "J41") (pin "1") (pinfunction "1_1") (pintype "passive"))
      (node (ref "J41") (pin "2") (pinfunction "2_2") (pintype "passive"))
      (node (ref "J41") (pin "3") (pinfunction "3_3") (pintype "passive"))
      (node (ref "J41") (pin "4") (pinfunction "4_4") (pintype "passive"))
      (node (ref "J41") (pin "5") (pinfunction "5_5") (pintype "passive"))
      (node (ref "J41") (pin "6") (pinfunction "6_6") (pintype "passive"))
      (node (ref "J41") (pin "7") (pinfunction "7_7") (pintype "passive"))
      (node (ref "J41") (pin "8") (pinfunction "8_8") (pintype "passive"))
    )
    (net (code "49") (name "Net-(J42-Pad1)") (class "Default")
      (node (ref "J42") (pin "1") (pinfunction "1_1") (pintype "passive"))
      (node (ref "J42") (pin "2") (pinfunction "2_2") (pintype "passive"))
      (node (ref "J42") (pin "3") (pinfunction "3_3") (pintype "passive"))
      (node (ref "J42") (pin "4") (pinfunction "4_4") (pintype "passive"))
      (node (ref "J42") (pin "5") (pinfunction "5_5") (pintype "passive"))
      (node (ref "J42") (pin "6") (pinfunction "6_6") (pintype "passive"))
      (node (ref "J42") (pin "7") (pinfunction "7_7") (pintype "passive"))
      (node (ref "J42") (pin "8") (pinfunction "8_8") (pintype "passive"))
    )
    (net (code "50") (name "Net-(J43-Pad1)") (class "Default")
      (node (ref "J43") (pin "1") (pinfunction "1_1") (pintype "passive"))
      (node (ref "J43") (pin "2") (pinfunction "2_2") (pintype "passive"))
      (node (ref "J43") (pin "3") (pinfunction "3_3") (pintype "passive"))
      (node (ref "J43") (pin "4") (pinfunction "4_4") (pintype "passive"))
      (node (ref "J43") (pin "5") (pinfunction "5_5") (pintype "passive"))
      (node (ref "J43") (pin "6") (pinfunction "6_6") (pintype "passive"))
      (node (ref "J43") (pin "7") (pinfunction "7_7") (pintype "passive"))
      (node (ref "J43") (pin "8") (pinfunction "8_8") (pintype "passive"))
    )
    (net (code "51") (name "Net-(LED4-PadA)") (class "Default")
      (node (ref "LED4") (pin "A") (pinfunction "A_A") (pintype "passive"))
      (node (ref "R6") (pin "1") (pinfunction "1_1") (pintype "passive"))
    )
    (net (code "52") (name "Net-(Q2-D)") (class "Default")
      (node (ref "Q2") (pin "3") (pinfunction "D_3") (pintype "passive"))
      (node (ref "U3") (pin "12") (pinfunction "RST_12") (pintype "bidirectional"))
    )
    (net (code "53") (name "Net-(U2-PROG)") (class "Default")
      (node (ref "R7") (pin "1") (pinfunction "1_1") (pintype "passive"))
      (node (ref "U2") (pin "5") (pinfunction "PROG_5") (pintype "input"))
    )
    (net (code "54") (name "Net-(U2-STAT)") (class "Default")
      (node (ref "R6") (pin "2") (pinfunction "2_2") (pintype "passive"))
      (node (ref "U2") (pin "1") (pinfunction "STAT_1") (pintype "output"))
    )
    (net (code "55") (name "Net-(U3-GSM_RF)") (class "Default")
      (node (ref "U3") (pin "35") (pinfunction "GSM_RF_35") (pintype "bidirectional"))
      (node (ref "X2") (pin "3") (pinfunction "SIGNAL_3") (pintype "passive"))
    )
    (net (code "56") (name "VCC") (class "Default")
      (node (ref "5V") (pin "1") (pinfunction "1_1") (pintype "passive"))
      (node (ref "C5") (pin "1") (pinfunction "1_1") (pintype "passive"))
      (node (ref "D1") (pin "C") (pinfunction "C_C") (pintype "passive"))
      (node (ref "J1") (pin "1") (pinfunction "1_1") (pintype "passive"))
      (node (ref "LED4") (pin "K") (pinfunction "C_K") (pintype "passive"))
      (node (ref "STD_MICROUSB") (pin "VBUS") (pinfunction "VBUS_VBUS") (pintype "power_in"))
      (node (ref "U1") (pin "1") (pinfunction "IN_1") (pintype "power_in"))
      (node (ref "U1") (pin "3") (pinfunction "EN_3") (pintype "input"))
      (node (ref "U2") (pin "4") (pinfunction "VDD_4") (pintype "power_in"))
    )
    (net (code "57") (name "V_BATT") (class "Default")
      (node (ref "C4") (pin "1") (pinfunction "1_1") (pintype "passive"))
      (node (ref "CN2") (pin "2") (pinfunction "2_2") (pintype "passive"))
      (node (ref "D1") (pin "A") (pinfunction "A_A") (pintype "passive"))
      (node (ref "U2") (pin "3") (pinfunction "VBAT_3") (pintype "power_in"))
    )
    (net (code "58") (name "unconnected-(DATAEXCHANGE-Pad2)") (class "Default")
      (node (ref "DATAEXCHANGE") (pin "2") (pinfunction "2_2") (pintype "passive"))
    )
    (net (code "59") (name "unconnected-(DATAEXCHANGE-Pad3)") (class "Default")
      (node (ref "DATAEXCHANGE") (pin "3") (pinfunction "3_3") (pintype "passive"))
    )
    (net (code "60") (name "unconnected-(DATAEXCHANGE-Pad6)") (class "Default")
      (node (ref "DATAEXCHANGE") (pin "6") (pinfunction "6_6") (pintype "passive"))
    )
    (net (code "61") (name "unconnected-(DEEPSLEEP-Pad1)") (class "Default")
      (node (ref "DEEPSLEEP") (pin "1") (pinfunction "1_1") (pintype "passive"))
    )
    (net (code "62") (name "unconnected-(SIMCARD-VPP-PadC6)") (class "Default")
      (node (ref "SIMCARD") (pin "C6") (pinfunction "VPP_C6") (pintype "input"))
    )
    (net (code "63") (name "unconnected-(STD_MICROUSB-PadD+)") (class "Default")
      (node (ref "STD_MICROUSB") (pin "D+") (pinfunction "D+_D+") (pintype "bidirectional"))
    )
    (net (code "64") (name "unconnected-(STD_MICROUSB-PadD-)") (class "Default")
      (node (ref "STD_MICROUSB") (pin "D-") (pinfunction "D-_D-") (pintype "bidirectional"))
    )
    (net (code "65") (name "unconnected-(STD_MICROUSB-PadID)") (class "Default")
      (node (ref "STD_MICROUSB") (pin "ID") (pinfunction "ID_ID") (pintype "bidirectional"))
    )
    (net (code "66") (name "unconnected-(U1-P4-Pad4)") (class "Default")
      (node (ref "U1") (pin "4") (pinfunction "P4_4") (pintype "bidirectional"))
    )
    (net (code "67") (name "unconnected-(U3-EAR_L-Pad23)") (class "Default")
      (node (ref "U3") (pin "23") (pinfunction "EAR_L_23") (pintype "bidirectional"))
    )
    (net (code "68") (name "unconnected-(U3-EAR_R-Pad24)") (class "Default")
      (node (ref "U3") (pin "24") (pinfunction "EAR_R_24") (pintype "bidirectional"))
    )
    (net (code "69") (name "unconnected-(U3-GPIO1{slash}INT-Pad9)") (class "Default")
      (node (ref "U3") (pin "9") (pinfunction "GPIO1/INT_9") (pintype "bidirectional"))
    )
    (net (code "70") (name "unconnected-(U3-GPIO6-Pad6)") (class "Default")
      (node (ref "U3") (pin "6") (pinfunction "GPIO6_6") (pintype "bidirectional"))
    )
    (net (code "71") (name "unconnected-(U3-GPIO7-Pad7)") (class "Default")
      (node (ref "U3") (pin "7") (pinfunction "GPIO7_7") (pintype "bidirectional"))
    )
    (net (code "72") (name "unconnected-(U3-GPIO13-Pad38)") (class "Default")
      (node (ref "U3") (pin "38") (pinfunction "GPIO13_38") (pintype "bidirectional"))
    )
    (net (code "73") (name "unconnected-(U3-GPIO14-Pad5)") (class "Default")
      (node (ref "U3") (pin "5") (pinfunction "GPIO14_5") (pintype "bidirectional"))
    )
    (net (code "74") (name "unconnected-(U3-GPIO15-Pad4)") (class "Default")
      (node (ref "U3") (pin "4") (pinfunction "GPIO15_4") (pintype "bidirectional"))
    )
    (net (code "75") (name "unconnected-(U3-GPIO16-Pad3)") (class "Default")
      (node (ref "U3") (pin "3") (pinfunction "GPIO16_3") (pintype "bidirectional"))
    )
    (net (code "76") (name "unconnected-(U3-GPS_RF-Pad1)") (class "Default")
      (node (ref "U3") (pin "1") (pinfunction "GPS_RF_1") (pintype "bidirectional"))
    )
    (net (code "77") (name "unconnected-(U3-GPS_TXD-Pad37)") (class "Default")
      (node (ref "U3") (pin "37") (pinfunction "GPS_TXD_37") (pintype "bidirectional"))
    )
    (net (code "78") (name "unconnected-(U3-HST_RXD-Pad32)") (class "Default")
      (node (ref "U3") (pin "32") (pinfunction "HST_RXD_32") (pintype "bidirectional"))
    )
    (net (code "79") (name "unconnected-(U3-HST_TXD-Pad33)") (class "Default")
      (node (ref "U3") (pin "33") (pinfunction "HST_TXD_33") (pintype "bidirectional"))
    )
    (net (code "80") (name "unconnected-(U3-MIC+-Pad20)") (class "Default")
      (node (ref "U3") (pin "20") (pinfunction "MIC+_20") (pintype "bidirectional"))
    )
    (net (code "81") (name "unconnected-(U3-MIC--Pad19)") (class "Default")
      (node (ref "U3") (pin "19") (pinfunction "MIC-_19") (pintype "bidirectional"))
    )
    (net (code "82") (name "unconnected-(U3-MIC2_P-Pad21)") (class "Default")
      (node (ref "U3") (pin "21") (pinfunction "MIC2_P_21") (pintype "bidirectional"))
    )
    (net (code "83") (name "unconnected-(U3-NC-Pad2)") (class "Default")
      (node (ref "U3") (pin "2") (pinfunction "NC_2") (pintype "bidirectional"))
    )
    (net (code "84") (name "unconnected-(U3-REC+-Pad26)") (class "Default")
      (node (ref "U3") (pin "26") (pinfunction "REC+_26") (pintype "bidirectional"))
    )
    (net (code "85") (name "unconnected-(U3-REC--Pad27)") (class "Default")
      (node (ref "U3") (pin "27") (pinfunction "REC-_27") (pintype "bidirectional"))
    )
    (net (code "86") (name "unconnected-(U3-UART_CTS{slash}GPIO5-Pad10)") (class "Default")
      (node (ref "U3") (pin "10") (pinfunction "UART_CTS/GPIO5_10") (pintype "bidirectional"))
    )
    (net (code "87") (name "unconnected-(U3-UART_RTS{slash}GPIO7-Pad11)") (class "Default")
      (node (ref "U3") (pin "11") (pinfunction "UART_RTS/GPIO7_11") (pintype "bidirectional"))
    )
    (net (code "88") (name "unconnected-(U3-VDD_1V8_OUT-Pad29)") (class "Default")
      (node (ref "U3") (pin "29") (pinfunction "VDD_1V8_OUT_29") (pintype "bidirectional"))
    )
    (net (code "89") (name "unconnected-(X1-CLK-Pad20)") (class "Default")
      (node (ref "X1") (pin "20") (pinfunction "CLK_20") (pintype "bidirectional"))
    )
    (net (code "90") (name "unconnected-(X1-CS-Pad17)") (class "Default")
      (node (ref "X1") (pin "17") (pinfunction "CS_17") (pintype "bidirectional"))
    )
    (net (code "91") (name "unconnected-(X1-DI-Pad21)") (class "Default")
      (node (ref "X1") (pin "21") (pinfunction "DI_21") (pintype "bidirectional"))
    )
    (net (code "92") (name "unconnected-(X1-DO-Pad18)") (class "Default")
      (node (ref "X1") (pin "18") (pinfunction "DO_18") (pintype "bidirectional"))
    )
    (net (code "93") (name "unconnected-(X1-GPIO9-Pad22)") (class "Default")
      (node (ref "X1") (pin "22") (pinfunction "GPIO9_22") (pintype "bidirectional"))
    )
    (net (code "94") (name "unconnected-(X1-GPIO10-Pad19)") (class "Default")
      (node (ref "X1") (pin "19") (pinfunction "GPIO10_19") (pintype "bidirectional"))
    )
  )
)
